# PROGRAMMER.net
KiCad netlist of a schematic drawn in Altium Designer
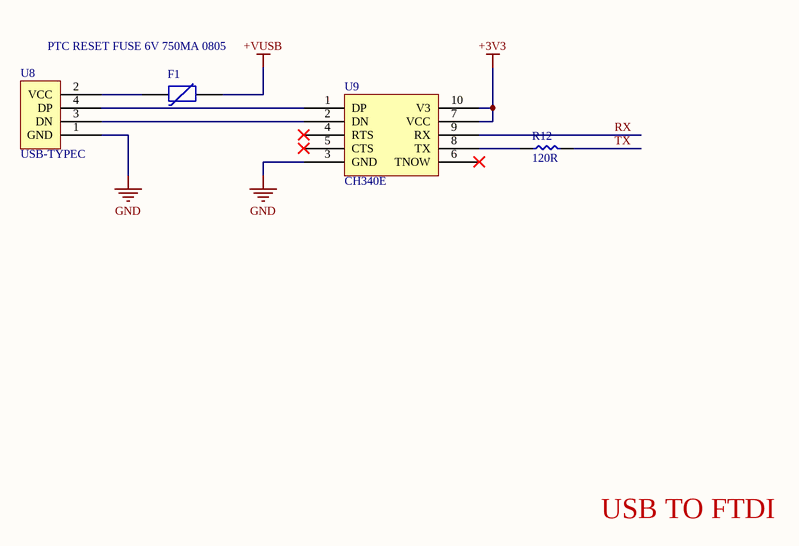
[diagram p0: PROGRAMMER.SchDoc]

(export (version "E")
  (design (tool "Eeschema 10.0.6"))
  (components
    (comp (ref "F1")
      (value "PTC RESET FUSE 6V 750MA 0805")
      (footprint "F0805L075SL")
      (fields
        (field (name "MANUFACTURER") "Littelfuse Inc.")
        (field (name "MANUFACTURER PART NUMBER") "0805L075SLYR")
      )
      (libsource (lib "salcox") (part "0805L075SLYR"))
    )
    (comp (ref "R12")
      (value "120R")
      (footprint "R0603")
      (description "RESISTOR, 0603, 120R, FULL REEL")
      (fields
        (field (name "MANUFACTURER") "Panasonic")
        (field (name "MANUFACTURER PART NUMBER") "ERA-3AEB121V")
      )
      (libsource (lib "salcox") (part "ERA-3AEB121V"))
    )
    (comp (ref "U8")
      (value "USB-TYPEC")
      (footprint "USB-TYPEC")
      (description "Conn Rcpt USB2.0 Typec 5A")
      (fields
        (field (name "MANUFACTURER") "Global Connector Technology")
        (field (name "MANUFACTURER PART NUMBER") "USB4105-GF-A")
      )
      (libsource (lib "salcox") (part "USB4105-GF-A"))
    )
    (comp (ref "U9")
      (value "CH340E")
      (footprint "MSOP-10")
      (fields
        (field (name "MANUFACTURER") "Eaton")
        (field (name "MANUFACTURER PART NUMBER") "EMCH340¦EMCH340")
      )
      (libsource (lib "salcox") (part "EMCH340"))
    )
  )
  (nets
    (net (code "1") (name "+3V3") (class "Default")
      (node (ref "U9") (pin "10") (pinfunction "V3_10") (pintype "passive"))
      (node (ref "U9") (pin "7") (pinfunction "VCC_7") (pintype "passive"))
    )
    (net (code "2") (name "+VUSB") (class "Default")
      (node (ref "F1") (pin "2") (pinfunction "2_2") (pintype "passive"))
    )
    (net (code "3") (name "/RX") (class "Default")
      (node (ref "U9") (pin "9") (pinfunction "RX_9") (pintype "passive"))
    )
    (net (code "4") (name "/TX") (class "Default")
      (node (ref "R12") (pin "2") (pinfunction "2_2") (pintype "passive"))
    )
    (net (code "5") (name "GND") (class "Default")
      (node (ref "U8") (pin "1") (pinfunction "GND_1") (pintype "passive"))
      (node (ref "U9") (pin "3") (pinfunction "GND_3") (pintype "passive"))
    )
    (net (code "6") (name "Net-(U8-DN)") (class "Default")
      (node (ref "U8") (pin "3") (pinfunction "DN_3") (pintype "passive"))
      (node (ref "U9") (pin "2") (pinfunction "DN_2") (pintype "passive"))
    )
    (net (code "7") (name "Net-(U8-DP)") (class "Default")
      (node (ref "U8") (pin "4") (pinfunction "DP_4") (pintype "passive"))
      (node (ref "U9") (pin "1") (pinfunction "DP_1") (pintype "passive"))
    )
    (net (code "8") (name "Net-(U8-VCC)") (class "Default")
      (node (ref "F1") (pin "1") (pinfunction "1_1") (pintype "passive"))
      (node (ref "U8") (pin "2") (pinfunction "VCC_2") (pintype "passive"))
    )
    (net (code "9") (name "Net-(U9-TX)") (class "Default")
      (node (ref "R12") (pin "1") (pinfunction "1_1") (pintype "passive"))
      (node (ref "U9") (pin "8") (pinfunction "TX_8") (pintype "passive"))
    )
    (net (code "10") (name "unconnected-(U9-CTS-Pad5)") (class "Default")
      (node (ref "U9") (pin "5") (pinfunction "CTS_5") (pintype "passive+no_connect"))
    )
    (net (code "11") (name "unconnected-(U9-RTS-Pad4)") (class "Default")
      (node (ref "U9") (pin "4") (pinfunction "RTS_4") (pintype "passive+no_connect"))
    )
    (net (code "12") (name "unconnected-(U9-TNOW-Pad6)") (class "Default")
      (node (ref "U9") (pin "6") (pinfunction "TNOW_6") (pintype "passive+no_connect"))
    )
  )
)
